# 08-RF_GPS.net
KiCad netlist of a schematic drawn in Altium Designer
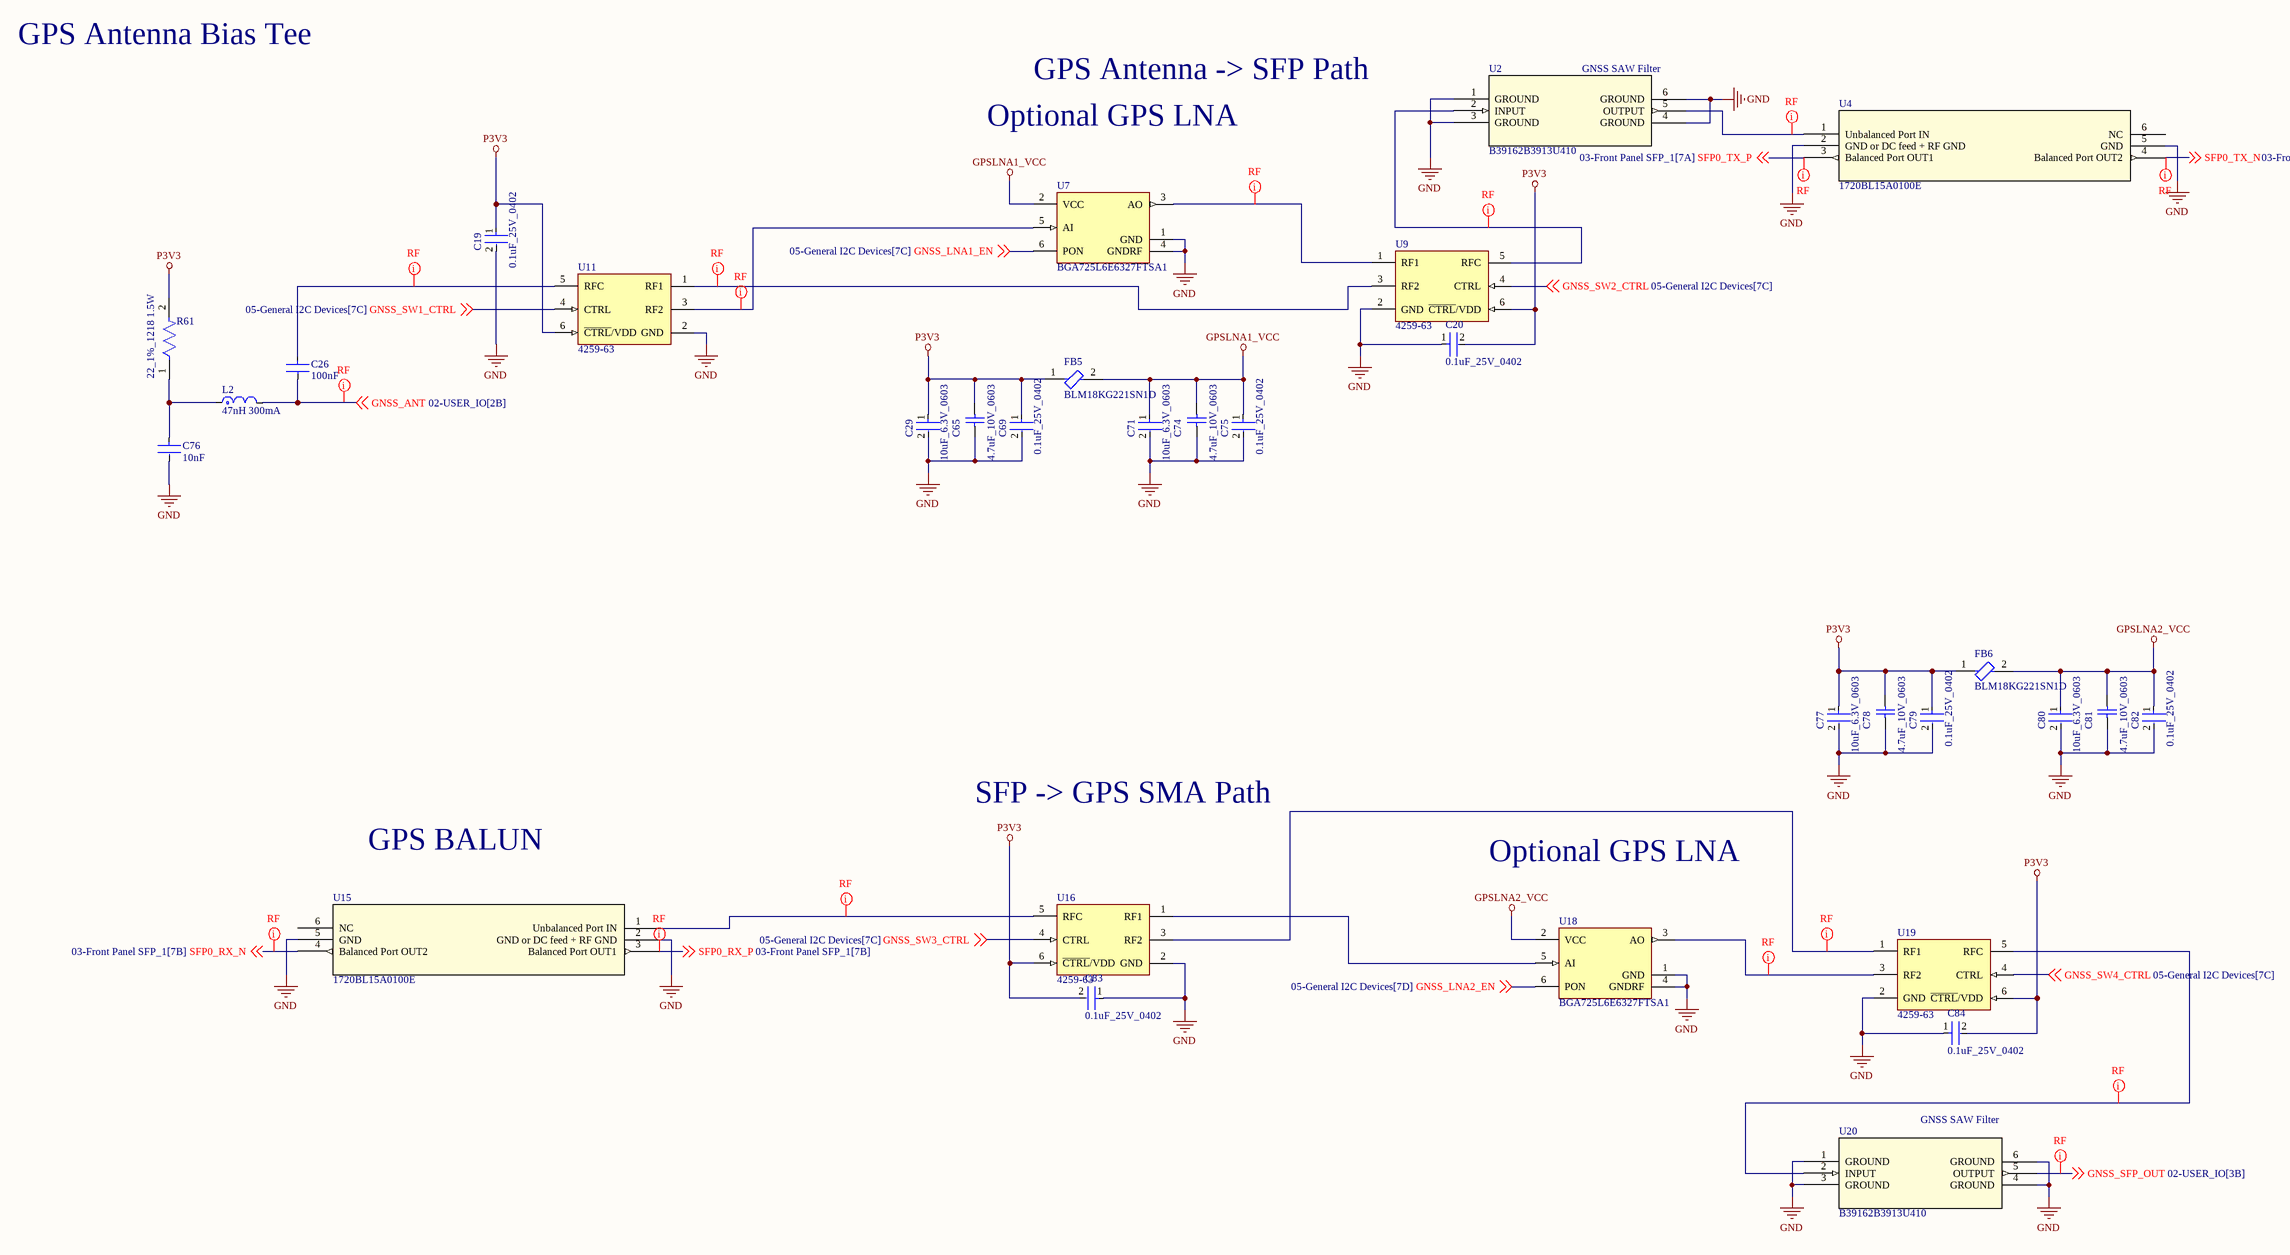
[diagram p0: 08-RF_GPS.SchDoc]

(export (version "E")
  (design (tool "Eeschema 10.0.6"))
  (components
    (comp (ref "C19")
      (value "0.1uF_25V_0402")
      (footprint "FP-0402-L_1_0_1-W_0_5_0_1-IPC_C")
      (description "General Purpose Ceramic Capacitor, 0402, 100nF, 10%, X7R, 15%, 25V")
      (fields (field (name "VOLTAGE") "25V") (field (name "TOLERANCE") "10%"))
      (libsource (lib "Altium Content Vault") (part "b4654b650e69147ec39a6b967a45e02"))
    )
    (comp (ref "C20")
      (value "0.1uF_25V_0402")
      (footprint "FP-0402-L_1_0_1-W_0_5_0_1-IPC_C")
      (description "General Purpose Ceramic Capacitor, 0402, 100nF, 10%, X7R, 15%, 25V")
      (fields (field (name "VOLTAGE") "25V") (field (name "TOLERANCE") "10%"))
      (libsource (lib "Altium Content Vault") (part "b4654b650e69147ec39a6b967a45e02"))
    )
    (comp (ref "C26")
      (value "100nF")
      (footprint "FP-0402-L_1_0_0_05-W_0_5-IPC_B")
      (description "None")
      (fields (field (name "TOLERANCE") "10%"))
      (libsource (lib "") (part "b4654b650e69147ec39a6b967a45e02_1"))
    )
    (comp (ref "C29")
      (value "10uF_6.3V_0603")
      (footprint "FP-C0603C106M9PACTU-MFG")
      (description "CAP CER 10UF 6.3V X5R 0603")
      (fields
        (field (name "MANUFACTURER PART NUMBER") "C0603C106M9PACTU")
        (field (name "MANUFACTURER") "Kemet")
      )
      (libsource (lib "Altium Content Vault") (part "b4654b650e69147ec39a6b967a45e02"))
    )
    (comp (ref "C65")
      (value "4.7uF_10V_0603")
      (footprint "CAPC1608X87X35NL15T15")
      (fields (field (name "PART NUMBER") "C0603C475K8PACTU") (field (name "MANUFACTURER") "Kemet"))
      (libsource (lib "Altium Content Vault") (part "CAP"))
    )
    (comp (ref "C69")
      (value "0.1uF_25V_0402")
      (footprint "FP-0402-L_1_0_1-W_0_5_0_1-IPC_C")
      (description "General Purpose Ceramic Capacitor, 0402, 100nF, 10%, X7R, 15%, 25V")
      (fields (field (name "VOLTAGE") "25V") (field (name "TOLERANCE") "10%"))
      (libsource (lib "Altium Content Vault") (part "b4654b650e69147ec39a6b967a45e02"))
    )
    (comp (ref "C71")
      (value "10uF_6.3V_0603")
      (footprint "FP-C0603C106M9PACTU-MFG")
      (description "CAP CER 10UF 6.3V X5R 0603")
      (fields
        (field (name "MANUFACTURER PART NUMBER") "C0603C106M9PACTU")
        (field (name "MANUFACTURER") "Kemet")
      )
      (libsource (lib "Altium Content Vault") (part "b4654b650e69147ec39a6b967a45e02"))
    )
    (comp (ref "C74")
      (value "4.7uF_10V_0603")
      (footprint "CAPC1608X87X35NL15T15")
      (fields (field (name "PART NUMBER") "C0603C475K8PACTU") (field (name "MANUFACTURER") "Kemet"))
      (libsource (lib "Altium Content Vault") (part "CAP"))
    )
    (comp (ref "C75")
      (value "0.1uF_25V_0402")
      (footprint "FP-0402-L_1_0_1-W_0_5_0_1-IPC_C")
      (description "General Purpose Ceramic Capacitor, 0402, 100nF, 10%, X7R, 15%, 25V")
      (fields (field (name "VOLTAGE") "25V") (field (name "TOLERANCE") "10%"))
      (libsource (lib "Altium Content Vault") (part "b4654b650e69147ec39a6b967a45e02"))
    )
    (comp (ref "C76")
      (value "10nF")
      (footprint "FP-GRM033-0_03-IPC_B")
      (description "Chip Multilayer Ceramic Capacitors for General Purpose, 0201, 10000pF, X7R, 15%, 10%, 16V")
      (fields (field (name "TOLERANCE") "10%"))
      (libsource (lib "") (part "b4654b650e69147ec39a6b967a45e02_1"))
    )
    (comp (ref "C77")
      (value "10uF_6.3V_0603")
      (footprint "FP-C0603C106M9PACTU-MFG")
      (description "CAP CER 10UF 6.3V X5R 0603")
      (fields
        (field (name "MANUFACTURER PART NUMBER") "C0603C106M9PACTU")
        (field (name "MANUFACTURER") "Kemet")
      )
      (libsource (lib "Altium Content Vault") (part "b4654b650e69147ec39a6b967a45e02"))
    )
    (comp (ref "C78")
      (value "4.7uF_10V_0603")
      (footprint "CAPC1608X87X35NL15T15")
      (fields (field (name "PART NUMBER") "C0603C475K8PACTU") (field (name "MANUFACTURER") "Kemet"))
      (libsource (lib "Altium Content Vault") (part "CAP"))
    )
    (comp (ref "C79")
      (value "0.1uF_25V_0402")
      (footprint "FP-0402-L_1_0_1-W_0_5_0_1-IPC_C")
      (description "General Purpose Ceramic Capacitor, 0402, 100nF, 10%, X7R, 15%, 25V")
      (fields (field (name "VOLTAGE") "25V") (field (name "TOLERANCE") "10%"))
      (libsource (lib "Altium Content Vault") (part "b4654b650e69147ec39a6b967a45e02"))
    )
    (comp (ref "C80")
      (value "10uF_6.3V_0603")
      (footprint "FP-C0603C106M9PACTU-MFG")
      (description "CAP CER 10UF 6.3V X5R 0603")
      (fields
        (field (name "MANUFACTURER PART NUMBER") "C0603C106M9PACTU")
        (field (name "MANUFACTURER") "Kemet")
      )
      (libsource (lib "Altium Content Vault") (part "b4654b650e69147ec39a6b967a45e02"))
    )
    (comp (ref "C81")
      (value "4.7uF_10V_0603")
      (footprint "CAPC1608X87X35NL15T15")
      (fields (field (name "PART NUMBER") "C0603C475K8PACTU") (field (name "MANUFACTURER") "Kemet"))
      (libsource (lib "Altium Content Vault") (part "CAP"))
    )
    (comp (ref "C82")
      (value "0.1uF_25V_0402")
      (footprint "FP-0402-L_1_0_1-W_0_5_0_1-IPC_C")
      (description "General Purpose Ceramic Capacitor, 0402, 100nF, 10%, X7R, 15%, 25V")
      (fields (field (name "VOLTAGE") "25V") (field (name "TOLERANCE") "10%"))
      (libsource (lib "Altium Content Vault") (part "b4654b650e69147ec39a6b967a45e02"))
    )
    (comp (ref "C83")
      (value "0.1uF_25V_0402")
      (footprint "FP-0402-L_1_0_1-W_0_5_0_1-IPC_C")
      (description "General Purpose Ceramic Capacitor, 0402, 100nF, 10%, X7R, 15%, 25V")
      (fields (field (name "VOLTAGE") "25V") (field (name "TOLERANCE") "10%"))
      (libsource (lib "Altium Content Vault") (part "b4654b650e69147ec39a6b967a45e02"))
    )
    (comp (ref "C84")
      (value "0.1uF_25V_0402")
      (footprint "FP-0402-L_1_0_1-W_0_5_0_1-IPC_C")
      (description "General Purpose Ceramic Capacitor, 0402, 100nF, 10%, X7R, 15%, 25V")
      (fields (field (name "VOLTAGE") "25V") (field (name "TOLERANCE") "10%"))
      (libsource (lib "Altium Content Vault") (part "b4654b650e69147ec39a6b967a45e02"))
    )
    (comp (ref "FB5")
      (value "BLM18KG221SN1D")
      (footprint "FP-BLM18-0_15-t0_8-IPC_B")
      (description "Chip Ferrite Bead, 0603, 220Ω @ 100MHz, 0.05Ω, 25%, 2.2A")
      (fields (field (name "TOLERANCE") "25%"))
      (libsource (lib "Altium Content Vault") (part "5f30dd21d616792df468990f7003faa"))
    )
    (comp (ref "FB6")
      (value "BLM18KG221SN1D")
      (footprint "FP-BLM18-0_15-t0_8-IPC_B")
      (description "Chip Ferrite Bead, 0603, 220Ω @ 100MHz, 0.05Ω, 25%, 2.2A")
      (fields (field (name "TOLERANCE") "25%"))
      (libsource (lib "Altium Content Vault") (part "5f30dd21d616792df468990f7003faa"))
    )
    (comp (ref "L2")
      (value "47nH 300mA")
      (footprint "FP-LQG15HH_02-IPC_B")
      (description "Multilayer type RF Inductor 47nH ±5% 0.72Ω 300mA 0402")
      (fields (field (name "TOLERANCE") "5%"))
      (libsource (lib "Altium Content Vault") (part "4cc4b267dca4c8e51f7102f422741d8"))
    )
    (comp (ref "R61")
      (value "22_1%_1218 1.5W")
      (footprint "FP-CRCW1218-HPe3-MFG")
      (description "RES Thick Film, 22.6Ω, 1%, 1.5W, 100ppm/°C, 1218")
      (fields (field (name "TOLERANCE") "1%"))
      (libsource (lib "Altium Content Vault") (part "1029c3af85768c4190bb7ad29bc67b5"))
    )
    (comp (ref "U2")
      (value "B39162B3913U410")
      (footprint "B39162B3913U410_QUA")
      (description "No Description Available")
      (libsource (lib "B39162B3913U410") (part "B39162B3913U410"))
    )
    (comp (ref "U4")
      (value "1720BL15A0100E")
      (footprint "SMT_15B0050E_JOT")
      (description "No Description Available")
      (libsource (lib "") (part "1720BL15A0100E_1"))
    )
    (comp (ref "U7")
      (value "BGA725L6E6327FTSA1")
      (footprint "FP-PG-TSLP-6-MFG")
      (description "IC AMP GPS 1.55-1.615GHZ TSLP6-2")
      (fields
        (field (name "OCTOPART") "https://octopart.com/bga725l6e6327ftsa1-infineon-23421878")
        (field (name "MANUFACTURER") "Infineon")
      )
      (libsource (lib "Altium Content Vault") (part "3fcdeb0a4b0737d1798366062040e11"))
    )
    (comp (ref "U9")
      (value "4259-63")
      (footprint "PERE-SC-70-6_M")
      (description "IC RF Switch SPDT, 50 Ohm, 6-Pin SC70, RoHS, Tape and Reel")
      (fields (field (name "MANUFACTURER") "Peregrine Semiconductor"))
      (libsource (lib "") (part "PERE-PE4259-6_1"))
    )
    (comp (ref "U11")
      (value "4259-63")
      (footprint "PERE-SC-70-6_M")
      (description "IC RF Switch SPDT, 50 Ohm, 6-Pin SC70, RoHS, Tape and Reel")
      (fields (field (name "MANUFACTURER") "Peregrine Semiconductor"))
      (libsource (lib "Altium Content Vault") (part "PERE-PE4259-6"))
    )
    (comp (ref "U15")
      (value "1720BL15A0100E")
      (footprint "SMT_15B0050E_JOT")
      (description "No Description Available")
      (libsource (lib "1720BL15A0100E") (part "1720BL15A0100E"))
    )
    (comp (ref "U16")
      (value "4259-63")
      (footprint "PERE-SC-70-6_M")
      (description "IC RF Switch SPDT, 50 Ohm, 6-Pin SC70, RoHS, Tape and Reel")
      (fields (field (name "MANUFACTURER") "Peregrine Semiconductor"))
      (libsource (lib "Altium Content Vault") (part "PERE-PE4259-6"))
    )
    (comp (ref "U18")
      (value "BGA725L6E6327FTSA1")
      (footprint "FP-PG-TSLP-6-MFG")
      (description "IC AMP GPS 1.55-1.615GHZ TSLP6-2")
      (fields
        (field (name "OCTOPART") "https://octopart.com/bga725l6e6327ftsa1-infineon-23421878")
        (field (name "MANUFACTURER") "Infineon")
      )
      (libsource (lib "Altium Content Vault") (part "3fcdeb0a4b0737d1798366062040e11"))
    )
    (comp (ref "U19")
      (value "4259-63")
      (footprint "PERE-SC-70-6_M")
      (description "IC RF Switch SPDT, 50 Ohm, 6-Pin SC70, RoHS, Tape and Reel")
      (fields (field (name "MANUFACTURER") "Peregrine Semiconductor"))
      (libsource (lib "") (part "PERE-PE4259-6_1"))
    )
    (comp (ref "U20")
      (value "B39162B3913U410")
      (footprint "B39162B3913U410_QUA")
      (description "No Description Available")
      (libsource (lib "B39162B3913U410") (part "B39162B3913U410"))
    )
  )
  (nets
    (net (code "1") (name "GND") (class "Default")
      (node (ref "C19") (pin "2") (pinfunction "2_2") (pintype "passive"))
      (node (ref "C20") (pin "1") (pinfunction "1_1") (pintype "passive"))
      (node (ref "C29") (pin "2") (pinfunction "2_2") (pintype "passive"))
      (node (ref "C65") (pin "1") (pinfunction "1_1") (pintype "passive"))
      (node (ref "C69") (pin "2") (pinfunction "2_2") (pintype "passive"))
      (node (ref "C71") (pin "2") (pinfunction "2_2") (pintype "passive"))
      (node (ref "C74") (pin "1") (pinfunction "1_1") (pintype "passive"))
      (node (ref "C75") (pin "2") (pinfunction "2_2") (pintype "passive"))
      (node (ref "C76") (pin "2") (pinfunction "2_2") (pintype "passive"))
      (node (ref "C77") (pin "2") (pinfunction "2_2") (pintype "passive"))
      (node (ref "C78") (pin "1") (pinfunction "1_1") (pintype "passive"))
      (node (ref "C79") (pin "2") (pinfunction "2_2") (pintype "passive"))
      (node (ref "C80") (pin "2") (pinfunction "2_2") (pintype "passive"))
      (node (ref "C81") (pin "1") (pinfunction "1_1") (pintype "passive"))
      (node (ref "C82") (pin "2") (pinfunction "2_2") (pintype "passive"))
      (node (ref "C83") (pin "1") (pinfunction "1_1") (pintype "passive"))
      (node (ref "C84") (pin "1") (pinfunction "1_1") (pintype "passive"))
      (node (ref "U11") (pin "2") (pinfunction "GND_2") (pintype "power_in"))
      (node (ref "U15") (pin "2") (pinfunction "GND_or_DC_feed_+_RF_GND_2") (pintype "power_in"))
      (node (ref "U15") (pin "5") (pinfunction "GND_5") (pintype "power_in"))
      (node (ref "U16") (pin "2") (pinfunction "GND_2") (pintype "power_in"))
      (node (ref "U18") (pin "1") (pinfunction "GND_1") (pintype "power_in"))
      (node (ref "U18") (pin "4") (pinfunction "GNDRF_4") (pintype "power_in"))
      (node (ref "U19") (pin "2") (pinfunction "GND_2") (pintype "power_in"))
      (node (ref "U2") (pin "1") (pinfunction "GROUND_1") (pintype "power_in"))
      (node (ref "U2") (pin "3") (pinfunction "GROUND_3") (pintype "power_in"))
      (node (ref "U2") (pin "4") (pinfunction "GROUND_4") (pintype "power_in"))
      (node (ref "U2") (pin "6") (pinfunction "GROUND_6") (pintype "power_in"))
      (node (ref "U20") (pin "1") (pinfunction "GROUND_1") (pintype "power_in"))
      (node (ref "U20") (pin "3") (pinfunction "GROUND_3") (pintype "power_in"))
      (node (ref "U20") (pin "4") (pinfunction "GROUND_4") (pintype "power_in"))
      (node (ref "U20") (pin "6") (pinfunction "GROUND_6") (pintype "power_in"))
      (node (ref "U4") (pin "2") (pinfunction "GND_or_DC_feed_+_RF_GND_2") (pintype "power_in"))
      (node (ref "U4") (pin "5") (pinfunction "GND_5") (pintype "power_in"))
      (node (ref "U7") (pin "1") (pinfunction "GND_1") (pintype "power_in"))
      (node (ref "U7") (pin "4") (pinfunction "GNDRF_4") (pintype "power_in"))
      (node (ref "U9") (pin "2") (pinfunction "GND_2") (pintype "power_in"))
    )
    (net (code "2") (name "GNSS_ANT") (class "Default")
      (node (ref "C26") (pin "2") (pinfunction "2_2") (pintype "passive"))
      (node (ref "L2") (pin "2") (pinfunction "2_2") (pintype "passive"))
    )
    (net (code "3") (name "GNSS_LNA1_EN") (class "Default")
      (node (ref "U7") (pin "6") (pinfunction "PON_6") (pintype "power_in"))
    )
    (net (code "4") (name "GNSS_LNA2_EN") (class "Default")
      (node (ref "U18") (pin "6") (pinfunction "PON_6") (pintype "power_in"))
    )
    (net (code "5") (name "GNSS_SFP_OUT") (class "Default")
      (node (ref "U20") (pin "5") (pinfunction "OUTPUT_5") (pintype "output"))
    )
    (net (code "6") (name "GNSS_SW1_CTRL") (class "Default")
      (node (ref "U11") (pin "4") (pinfunction "CTRL_4") (pintype "input"))
    )
    (net (code "7") (name "GNSS_SW2_CTRL") (class "Default")
      (node (ref "U9") (pin "4") (pinfunction "CTRL_4") (pintype "input"))
    )
    (net (code "8") (name "GNSS_SW3_CTRL") (class "Default")
      (node (ref "U16") (pin "4") (pinfunction "CTRL_4") (pintype "input"))
    )
    (net (code "9") (name "GNSS_SW4_CTRL") (class "Default")
      (node (ref "U19") (pin "4") (pinfunction "CTRL_4") (pintype "input"))
    )
    (net (code "10") (name "GPSLNA1_VCC") (class "Default")
      (node (ref "C71") (pin "1") (pinfunction "1_1") (pintype "passive"))
      (node (ref "C74") (pin "2") (pinfunction "2_2") (pintype "passive"))
      (node (ref "C75") (pin "1") (pinfunction "1_1") (pintype "passive"))
      (node (ref "FB5") (pin "2") (pinfunction "2_2") (pintype "passive"))
      (node (ref "U7") (pin "2") (pinfunction "VCC_2") (pintype "power_in"))
    )
    (net (code "11") (name "GPSLNA2_VCC") (class "Default")
      (node (ref "C80") (pin "1") (pinfunction "1_1") (pintype "passive"))
      (node (ref "C81") (pin "2") (pinfunction "2_2") (pintype "passive"))
      (node (ref "C82") (pin "1") (pinfunction "1_1") (pintype "passive"))
      (node (ref "FB6") (pin "2") (pinfunction "2_2") (pintype "passive"))
      (node (ref "U18") (pin "2") (pinfunction "VCC_2") (pintype "power_in"))
    )
    (net (code "12") (name "Net-(C76-Pad1)") (class "Default")
      (node (ref "C76") (pin "1") (pinfunction "1_1") (pintype "passive"))
      (node (ref "L2") (pin "1") (pinfunction "1_1") (pintype "passive"))
      (node (ref "R61") (pin "1") (pinfunction "1_1") (pintype "passive"))
    )
    (net (code "13") (name "Net-(U2-INPUT)") (class "Default")
      (node (ref "U2") (pin "2") (pinfunction "INPUT_2") (pintype "input"))
      (node (ref "U9") (pin "5") (pinfunction "RFC_5") (pintype "passive"))
    )
    (net (code "14") (name "Net-(U2-OUTPUT)") (class "Default")
      (node (ref "U2") (pin "5") (pinfunction "OUTPUT_5") (pintype "output"))
      (node (ref "U4") (pin "1") (pinfunction "Unbalanced_Port_IN_1") (pintype "passive"))
    )
    (net (code "15") (name "Net-(U7-AO)") (class "Default")
      (node (ref "U7") (pin "3") (pinfunction "AO_3") (pintype "output"))
      (node (ref "U9") (pin "1") (pinfunction "RF1_1") (pintype "passive"))
    )
    (net (code "16") (name "Net-(U11-RF1)") (class "Default")
      (node (ref "U11") (pin "1") (pinfunction "RF1_1") (pintype "passive"))
      (node (ref "U9") (pin "3") (pinfunction "RF2_3") (pintype "passive"))
    )
    (net (code "17") (name "Net-(U11-RF2)") (class "Default")
      (node (ref "U11") (pin "3") (pinfunction "RF2_3") (pintype "passive"))
      (node (ref "U7") (pin "5") (pinfunction "AI_5") (pintype "input"))
    )
    (net (code "18") (name "Net-(U11-RFC)") (class "Default")
      (node (ref "C26") (pin "1") (pinfunction "1_1") (pintype "passive"))
      (node (ref "U11") (pin "5") (pinfunction "RFC_5") (pintype "passive"))
    )
    (net (code "19") (name "Net-(U15-Unbalanced_Port_IN)") (class "Default")
      (node (ref "U15") (pin "1") (pinfunction "Unbalanced_Port_IN_1") (pintype "passive"))
      (node (ref "U16") (pin "5") (pinfunction "RFC_5") (pintype "passive"))
    )
    (net (code "20") (name "Net-(U16-RF1)") (class "Default")
      (node (ref "U16") (pin "1") (pinfunction "RF1_1") (pintype "passive"))
      (node (ref "U18") (pin "5") (pinfunction "AI_5") (pintype "input"))
    )
    (net (code "21") (name "Net-(U16-RF2)") (class "Default")
      (node (ref "U16") (pin "3") (pinfunction "RF2_3") (pintype "passive"))
      (node (ref "U19") (pin "1") (pinfunction "RF1_1") (pintype "passive"))
    )
    (net (code "22") (name "Net-(U18-AO)") (class "Default")
      (node (ref "U18") (pin "3") (pinfunction "AO_3") (pintype "output"))
      (node (ref "U19") (pin "3") (pinfunction "RF2_3") (pintype "passive"))
    )
    (net (code "23") (name "Net-(U19-RFC)") (class "Default")
      (node (ref "U19") (pin "5") (pinfunction "RFC_5") (pintype "passive"))
      (node (ref "U20") (pin "2") (pinfunction "INPUT_2") (pintype "input"))
    )
    (net (code "24") (name "P3V3") (class "Default")
      (node (ref "C19") (pin "1") (pinfunction "1_1") (pintype "passive"))
      (node (ref "C20") (pin "2") (pinfunction "2_2") (pintype "passive"))
      (node (ref "C29") (pin "1") (pinfunction "1_1") (pintype "passive"))
      (node (ref "C65") (pin "2") (pinfunction "2_2") (pintype "passive"))
      (node (ref "C69") (pin "1") (pinfunction "1_1") (pintype "passive"))
      (node (ref "C77") (pin "1") (pinfunction "1_1") (pintype "passive"))
      (node (ref "C78") (pin "2") (pinfunction "2_2") (pintype "passive"))
      (node (ref "C79") (pin "1") (pinfunction "1_1") (pintype "passive"))
      (node (ref "C83") (pin "2") (pinfunction "2_2") (pintype "passive"))
      (node (ref "C84") (pin "2") (pinfunction "2_2") (pintype "passive"))
      (node (ref "FB5") (pin "1") (pinfunction "1_1") (pintype "passive"))
      (node (ref "FB6") (pin "1") (pinfunction "1_1") (pintype "passive"))
      (node (ref "R61") (pin "2") (pinfunction "2_2") (pintype "passive"))
      (node (ref "U11") (pin "6") (pinfunction "~{CTRL}/VDD_6") (pintype "input"))
      (node (ref "U16") (pin "6") (pinfunction "~{CTRL}/VDD_6") (pintype "input"))
      (node (ref "U19") (pin "6") (pinfunction "~{CTRL}/VDD_6") (pintype "input"))
      (node (ref "U9") (pin "6") (pinfunction "~{CTRL}/VDD_6") (pintype "input"))
    )
    (net (code "25") (name "SFP0_RX_N") (class "Default")
      (node (ref "U15") (pin "4") (pinfunction "Balanced_Port_OUT2_4") (pintype "output"))
    )
    (net (code "26") (name "SFP0_RX_P") (class "Default")
      (node (ref "U15") (pin "3") (pinfunction "Balanced_Port_OUT1_3") (pintype "output"))
    )
    (net (code "27") (name "SFP0_TX_N") (class "Default")
      (node (ref "U4") (pin "4") (pinfunction "Balanced_Port_OUT2_4") (pintype "output"))
    )
    (net (code "28") (name "SFP0_TX_P") (class "Default")
      (node (ref "U4") (pin "3") (pinfunction "Balanced_Port_OUT1_3") (pintype "output"))
    )
    (net (code "29") (name "unconnected-(U4-NC-Pad6)") (class "Default")
      (node (ref "U4") (pin "6") (pinfunction "NC_6") (pintype "passive"))
    )
    (net (code "30") (name "unconnected-(U15-NC-Pad6)") (class "Default")
      (node (ref "U15") (pin "6") (pinfunction "NC_6") (pintype "passive"))
    )
  )
)
